# RS232_2.net
KiCad netlist of a schematic drawn in Altium Designer
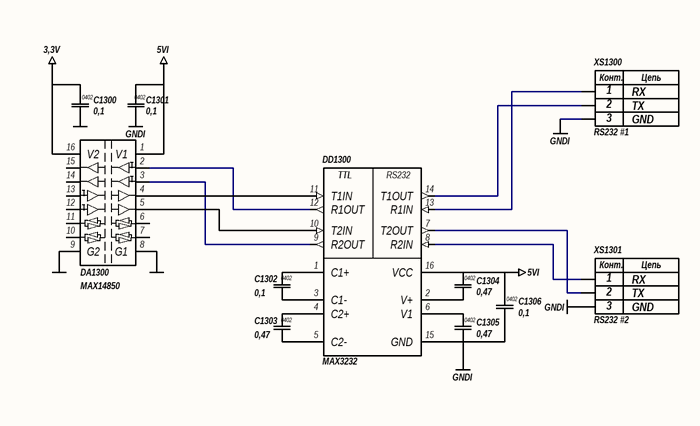
[diagram p0: RS232 2 кан..SchDoc]

(export (version "E")
  (design (tool "Eeschema 10.0.6"))
  (components
    (comp (ref "C1300")
      (value "0,1")
      (footprint "CAP0402")
      (description "Конденсатор чип")
      (libsource (lib "EwgPassive") (part "CAP_0402"))
    )
    (comp (ref "C1301")
      (value "0,1")
      (footprint "CAP0402")
      (description "Конденсатор чип")
      (libsource (lib "EwgPassive") (part "CAP_0402"))
    )
    (comp (ref "C1302")
      (value "0,1")
      (footprint "CAP0402")
      (description "Конденсатор чип")
      (libsource (lib "EwgPassive") (part "CAP_0402"))
    )
    (comp (ref "C1303")
      (value "0,47")
      (footprint "CAP0402")
      (description "Конденсатор чип")
      (libsource (lib "EwgPassive") (part "CAP_0402"))
    )
    (comp (ref "C1304")
      (value "0,47")
      (footprint "CAP0402")
      (description "Конденсатор чип")
      (libsource (lib "EwgPassive") (part "CAP_0402"))
    )
    (comp (ref "C1305")
      (value "0,47")
      (footprint "CAP0402")
      (description "Конденсатор чип")
      (libsource (lib "EwgPassive") (part "CAP_0402"))
    )
    (comp (ref "C1306")
      (value "0,1")
      (footprint "CAP0402")
      (description "Конденсатор чип")
      (libsource (lib "EwgPassive") (part "CAP_0402"))
    )
    (comp (ref "DA1300")
      (value "MAX14850")
      (footprint "SO16")
      (description "Цифровой изолятор 2 вх 2 вых 2 вх/вых")
      (libsource (lib "EwgOpto") (part "MAX14850"))
    )
    (comp (ref "DD1300")
      (value "MAX3232")
      (footprint "SO16-3.9")
      (description "Интерфейс RS232 2 кан.")
      (libsource (lib "EwgMicrochips") (part "MAX3232"))
    )
    (comp (ref "XS1300")
      (value "RS232 #1")
      (footprint "MW-3M")
      (description "Разъем")
      (libsource (lib "EwgConnectors") (part "Разъем3_1"))
    )
    (comp (ref "XS1301")
      (value "RS232 #2")
      (footprint "MW-3M")
      (description "Разъем")
      (libsource (lib "EwgConnectors") (part "Разъем3_1"))
    )
  )
  (nets
    (net (code "1") (name "3,3V") (class "Default")
      (node (ref "C1300") (pin "1") (pintype "passive"))
      (node (ref "DA1300") (pin "16") (pinfunction "V2_16") (pintype "power_in"))
    )
    (net (code "2") (name "5VI") (class "Default")
      (node (ref "C1301") (pin "1") (pintype "passive"))
      (node (ref "C1304") (pin "1") (pintype "passive"))
      (node (ref "C1306") (pin "1") (pintype "passive"))
      (node (ref "DA1300") (pin "1") (pinfunction "V1_1") (pintype "power_in"))
      (node (ref "DD1300") (pin "16") (pinfunction "VCC_16") (pintype "passive"))
    )
    (net (code "3") (name "GND") (class "Default")
      (node (ref "C1300") (pin "2") (pintype "passive"))
      (node (ref "DA1300") (pin "8") (pinfunction "G1_8") (pintype "passive"))
      (node (ref "DA1300") (pin "9") (pinfunction "G2_9") (pintype "passive"))
    )
    (net (code "4") (name "GNDI") (class "Default")
      (node (ref "C1301") (pin "2") (pintype "passive"))
      (node (ref "C1305") (pin "2") (pintype "passive"))
      (node (ref "C1306") (pin "2") (pintype "passive"))
      (node (ref "DD1300") (pin "15") (pinfunction "GND_15") (pintype "passive"))
      (node (ref "XS1300") (pin "3") (pinfunction "GND_3") (pintype "passive"))
      (node (ref "XS1301") (pin "3") (pinfunction "GND_3") (pintype "passive"))
    )
    (net (code "5") (name "Net-(DA1300-INA)") (class "Default")
      (node (ref "DA1300") (pin "3") (pinfunction "INA_3") (pintype "passive"))
      (node (ref "DD1300") (pin "9") (pinfunction "R2OUT_9") (pintype "output"))
    )
    (net (code "6") (name "Net-(DA1300-INB)") (class "Default")
      (node (ref "DA1300") (pin "4") (pinfunction "INB_4") (pintype "passive"))
      (node (ref "DD1300") (pin "11") (pinfunction "T1IN_11") (pintype "input"))
    )
    (net (code "7") (name "Net-(DA1300-OUTC)") (class "Default")
      (node (ref "DA1300") (pin "5") (pinfunction "OUTC_5") (pintype "passive"))
      (node (ref "DD1300") (pin "10") (pinfunction "T2IN_10") (pintype "input"))
    )
    (net (code "8") (name "Net-(DD1300-C1+)") (class "Default")
      (node (ref "C1302") (pin "1") (pintype "passive"))
      (node (ref "DD1300") (pin "1") (pinfunction "C1+_1") (pintype "passive"))
    )
    (net (code "9") (name "Net-(DD1300-C1-)") (class "Default")
      (node (ref "C1302") (pin "2") (pintype "passive"))
      (node (ref "DD1300") (pin "3") (pinfunction "C1-_3") (pintype "passive"))
    )
    (net (code "10") (name "Net-(DD1300-C2+)") (class "Default")
      (node (ref "C1303") (pin "1") (pintype "passive"))
      (node (ref "DD1300") (pin "4") (pinfunction "C2+_4") (pintype "passive"))
    )
    (net (code "11") (name "Net-(DD1300-C2-)") (class "Default")
      (node (ref "C1303") (pin "2") (pintype "passive"))
      (node (ref "DD1300") (pin "5") (pinfunction "C2-_5") (pintype "passive"))
    )
    (net (code "12") (name "Net-(DD1300-R1IN)") (class "Default")
      (node (ref "DD1300") (pin "13") (pinfunction "R1IN_13") (pintype "input"))
      (node (ref "XS1300") (pin "1") (pinfunction "RX_1") (pintype "passive"))
    )
    (net (code "13") (name "Net-(DD1300-R1OUT)") (class "Default")
      (node (ref "DA1300") (pin "2") (pintype "power_in"))
      (node (ref "DD1300") (pin "12") (pinfunction "R1OUT_12") (pintype "output"))
    )
    (net (code "14") (name "Net-(DD1300-R2IN)") (class "Default")
      (node (ref "DD1300") (pin "8") (pinfunction "R2IN_8") (pintype "input"))
      (node (ref "XS1301") (pin "1") (pinfunction "RX_1") (pintype "passive"))
    )
    (net (code "15") (name "Net-(DD1300-T1OUT)") (class "Default")
      (node (ref "DD1300") (pin "14") (pinfunction "T1OUT_14") (pintype "output"))
      (node (ref "XS1300") (pin "2") (pinfunction "TX_2") (pintype "passive"))
    )
    (net (code "16") (name "Net-(DD1300-T2OUT)") (class "Default")
      (node (ref "DD1300") (pin "7") (pinfunction "T2OUT_7") (pintype "output"))
      (node (ref "XS1301") (pin "2") (pinfunction "TX_2") (pintype "passive"))
    )
    (net (code "17") (name "Net-(DD1300-V+)") (class "Default")
      (node (ref "C1304") (pin "2") (pintype "passive"))
      (node (ref "DD1300") (pin "2") (pinfunction "V+_2") (pintype "passive"))
    )
    (net (code "18") (name "Net-(DD1300-V1)") (class "Default")
      (node (ref "C1305") (pin "1") (pintype "passive"))
      (node (ref "DD1300") (pin "6") (pinfunction "V1_6") (pintype "passive"))
    )
    (net (code "19") (name "unconnected-(DA1300-E2-Pad10)") (class "Default")
      (node (ref "DA1300") (pin "10") (pinfunction "E2_10") (pintype "passive"))
    )
    (net (code "20") (name "unconnected-(DA1300-EN1-Pad7)") (class "Default")
      (node (ref "DA1300") (pin "7") (pinfunction "EN1_7") (pintype "passive"))
    )
    (net (code "21") (name "unconnected-(DA1300-NC-Pad6)") (class "Default")
      (node (ref "DA1300") (pin "6") (pinfunction "NC_6") (pintype "passive"))
    )
    (net (code "22") (name "unconnected-(DA1300-Pad11)") (class "Default")
      (node (ref "DA1300") (pin "11") (pintype "passive"))
    )
    (net (code "23") (name "unconnected-(DA1300-Pad12)") (class "Default")
      (node (ref "DA1300") (pin "12") (pintype "passive"))
    )
    (net (code "24") (name "unconnected-(DA1300-Pad13)") (class "Default")
      (node (ref "DA1300") (pin "13") (pintype "passive"))
    )
    (net (code "25") (name "unconnected-(DA1300-Pad14)") (class "Default")
      (node (ref "DA1300") (pin "14") (pintype "passive"))
    )
    (net (code "26") (name "unconnected-(DA1300-Pad15)") (class "Default")
      (node (ref "DA1300") (pin "15") (pintype "power_in"))
    )
  )
)
